# MySensors_AirQuality_Board_2017-11-14.net
KiCad netlist of a schematic drawn in EAGLE
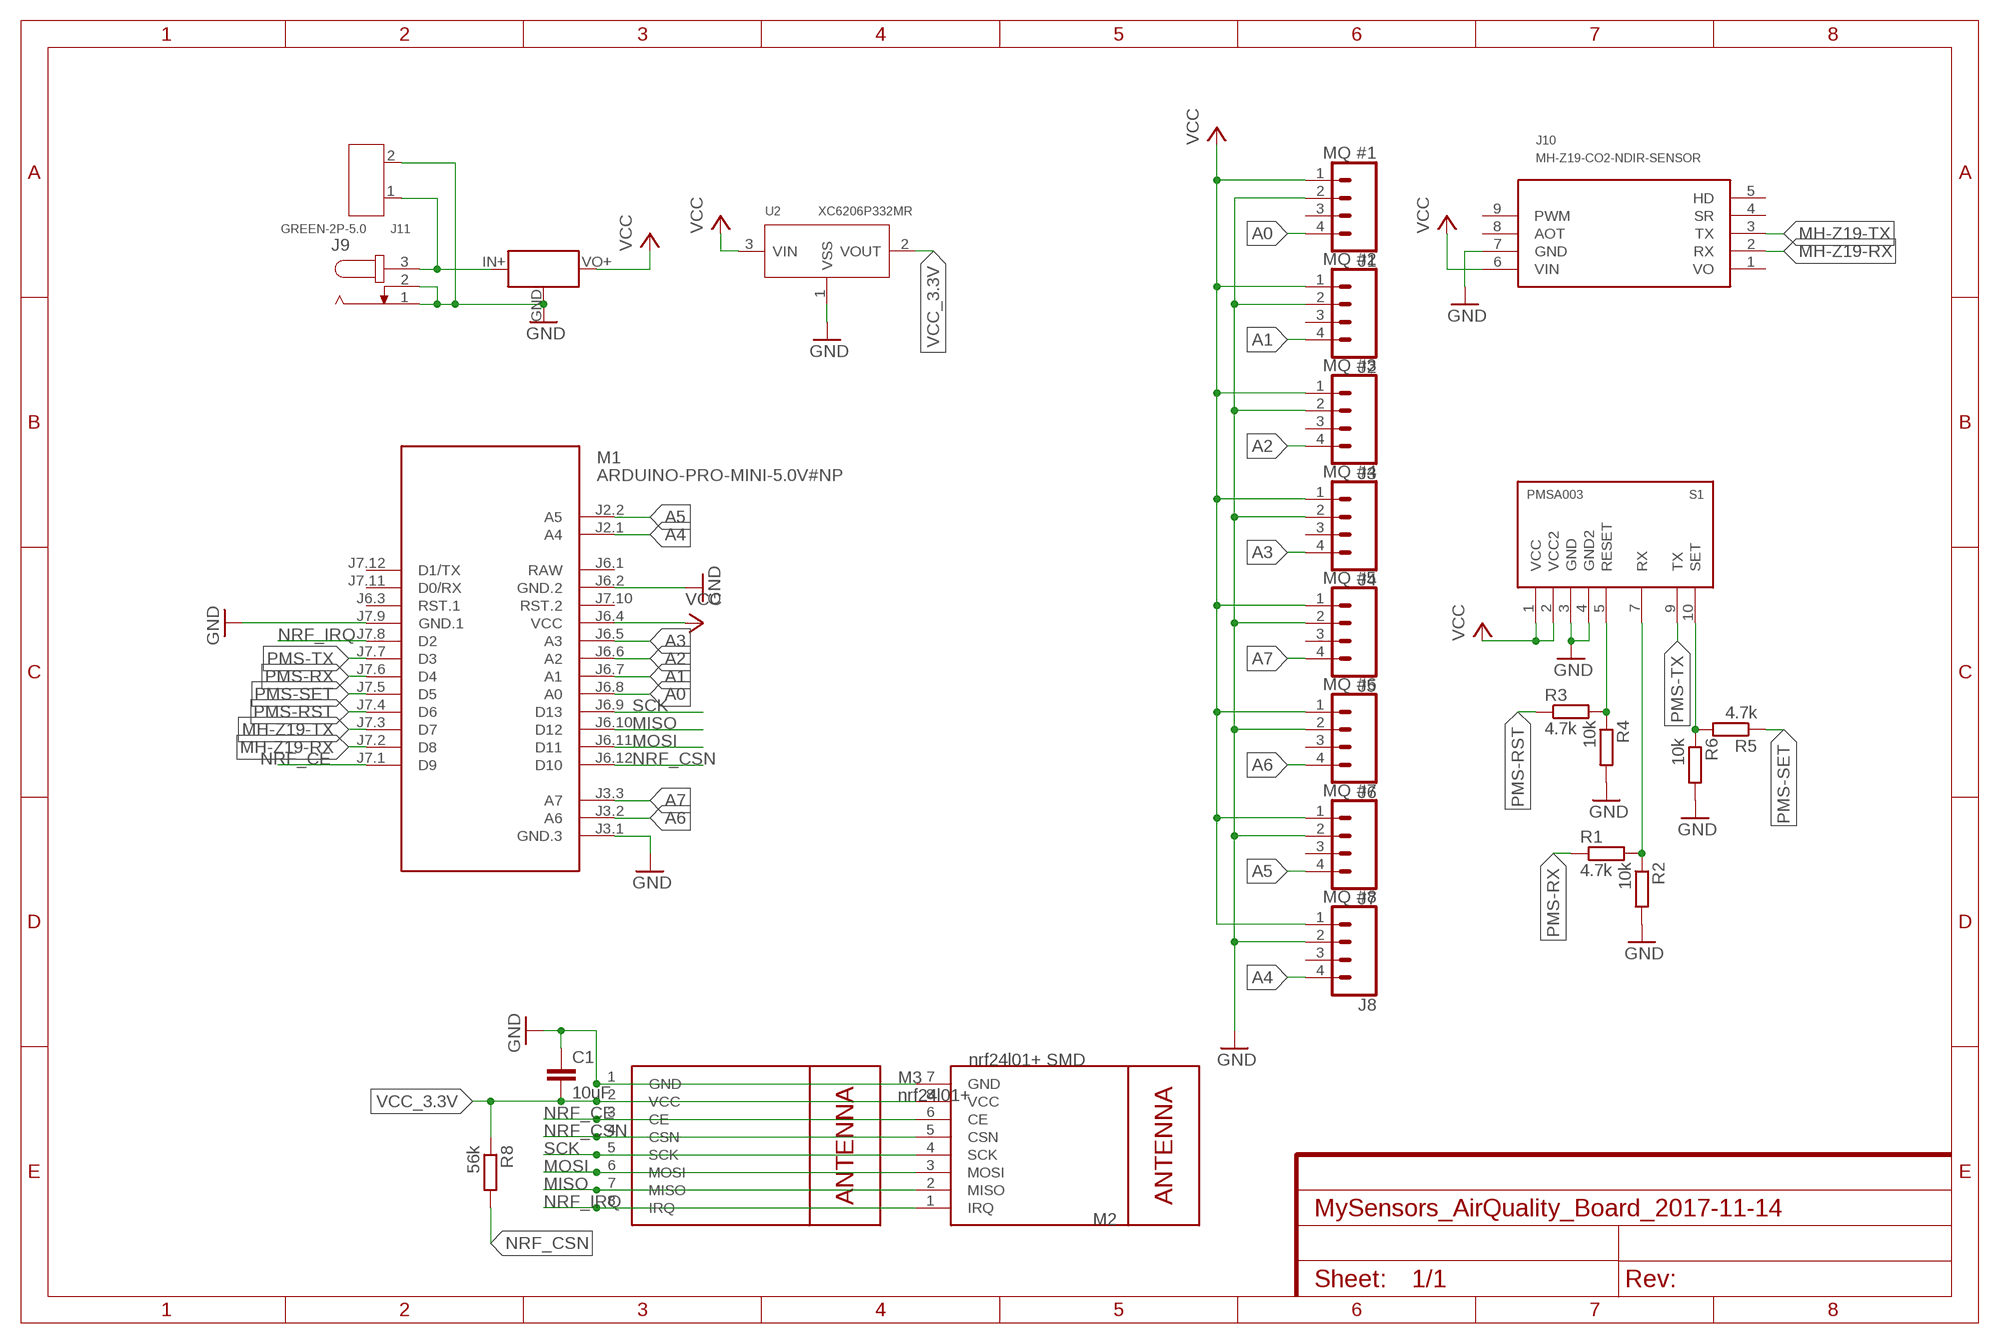
[diagram p0: schematic, sheet 1]

(export (version "E")
  (design (tool "Eeschema 10.0.6"))
  (components
    (comp (ref "C1")
      (value "10uF")
      (footprint "eagle-import:C0805")
      (libsource (lib "eagle-import") (part "C-EUC0805"))
    )
    (comp (ref "J1")
      (value "MQ #1")
      (footprint "eagle-import:1X04")
      (libsource (lib "eagle-import") (part "CONN_04"))
    )
    (comp (ref "J2")
      (value "MQ #2")
      (footprint "eagle-import:1X04")
      (libsource (lib "eagle-import") (part "CONN_04"))
    )
    (comp (ref "J3")
      (value "MQ #3")
      (footprint "eagle-import:1X04")
      (libsource (lib "eagle-import") (part "CONN_04"))
    )
    (comp (ref "J4")
      (value "MQ #4")
      (footprint "eagle-import:1X04")
      (libsource (lib "eagle-import") (part "CONN_04"))
    )
    (comp (ref "J5")
      (value "MQ #5")
      (footprint "eagle-import:1X04")
      (libsource (lib "eagle-import") (part "CONN_04"))
    )
    (comp (ref "J6")
      (value "MQ #6")
      (footprint "eagle-import:1X04")
      (libsource (lib "eagle-import") (part "CONN_04"))
    )
    (comp (ref "J7")
      (value "MQ #7")
      (footprint "eagle-import:1X04")
      (libsource (lib "eagle-import") (part "CONN_04"))
    )
    (comp (ref "J8")
      (value "MQ #8")
      (footprint "eagle-import:1X04")
      (libsource (lib "eagle-import") (part "CONN_04"))
    )
    (comp (ref "J9")
      (value "JACK-PLUG1")
      (footprint "eagle-import:SPC4078")
      (libsource (lib "eagle-import") (part "JACK-PLUG1"))
    )
    (comp (ref "J10")
      (value "MH-Z19-CO2-NDIR-SENSOR")
      (footprint "eagle-import:MH-Z19")
      (libsource (lib "eagle-import") (part "MH-Z19-CO2-NDIR-SENSOR"))
    )
    (comp (ref "J11")
      (value "GREEN-2P-5.0")
      (footprint "eagle-import:H2-5.0-10.5X8.0MM")
      (libsource (lib "eagle-import") (part "SCREW-TERMINAL-GREEN(2P-5.0)"))
    )
    (comp (ref "M1")
      (value "ARDUINO-PRO-MINI-5.0V#NP")
      (footprint "eagle-import:ARDUINO-PRO-MINI#NP")
      (libsource (lib "eagle-import") (part "ARDUINO-PRO-MINI-#NP5.0V"))
    )
    (comp (ref "M2")
      (value "nrf24l01+ SMD")
      (footprint "eagle-import:WIRELESS-NRF24L01-SMD")
      (libsource (lib "eagle-import") (part "WIRELESS-NRF24L01SMD"))
    )
    (comp (ref "M3")
      (value "nrf24l01+")
      (footprint "eagle-import:WIRELESS-NRF24L01")
      (libsource (lib "eagle-import") (part "WIRELESS-NRF24L01STANDARD"))
    )
    (comp (ref "R1")
      (value "4.7k")
      (footprint "eagle-import:R0805")
      (libsource (lib "eagle-import") (part "resistor_348_R-EU_R0805"))
    )
    (comp (ref "R2")
      (value "10k")
      (footprint "eagle-import:R0805")
      (libsource (lib "eagle-import") (part "resistor_348_R-EU_R0805"))
    )
    (comp (ref "R3")
      (value "4.7k")
      (footprint "eagle-import:R0805")
      (libsource (lib "eagle-import") (part "resistor_348_R-EU_R0805"))
    )
    (comp (ref "R4")
      (value "10k")
      (footprint "eagle-import:R0805")
      (libsource (lib "eagle-import") (part "resistor_348_R-EU_R0805"))
    )
    (comp (ref "R5")
      (value "4.7k")
      (footprint "eagle-import:R0805")
      (libsource (lib "eagle-import") (part "resistor_348_R-EU_R0805"))
    )
    (comp (ref "R6")
      (value "10k")
      (footprint "eagle-import:R0805")
      (libsource (lib "eagle-import") (part "resistor_348_R-EU_R0805"))
    )
    (comp (ref "R8")
      (value "56k")
      (footprint "eagle-import:R0805")
      (libsource (lib "eagle-import") (part "R-EU_R0805"))
    )
    (comp (ref "S1")
      (value "PMSA003")
      (footprint "eagle-import:PMSA003")
      (libsource (lib "eagle-import") (part "PMSA003"))
    )
    (comp (ref "U$2")
      (value "MINI_BUCK_CONVERTER")
      (footprint "eagle-import:MINI_BUCK_CONVERTER")
      (libsource (lib "eagle-import") (part "MINI_BUCK_CONVERTER"))
    )
    (comp (ref "U2")
      (value "XC6206P332MR")
      (footprint "eagle-import:SOT-23")
      (fields (field (name "MPN") "XC6206P332MR-G"))
      (libsource (lib "eagle-import") (part "PMIC-LDO-XC6206P332MR-G(SOT23)"))
    )
  )
  (nets
    (net (code "1") (name "/MISO") (class "Default")
      (node (ref "M1") (pin "J6.10") (pinfunction "D12_J6.10") (pintype "bidirectional"))
      (node (ref "M2") (pin "2") (pinfunction "MISO_2") (pintype "bidirectional"))
      (node (ref "M3") (pin "7") (pinfunction "MISO_7") (pintype "bidirectional"))
    )
    (net (code "2") (name "/MOSI") (class "Default")
      (node (ref "M1") (pin "J6.11") (pinfunction "D11_J6.11") (pintype "bidirectional"))
      (node (ref "M2") (pin "3") (pinfunction "MOSI_3") (pintype "bidirectional"))
      (node (ref "M3") (pin "6") (pinfunction "MOSI_6") (pintype "bidirectional"))
    )
    (net (code "3") (name "/NRF_CE") (class "Default")
      (node (ref "M1") (pin "J7.1") (pinfunction "D9_J7.1") (pintype "bidirectional"))
      (node (ref "M2") (pin "6") (pinfunction "CE_6") (pintype "bidirectional"))
      (node (ref "M3") (pin "3") (pinfunction "CE_3") (pintype "bidirectional"))
    )
    (net (code "4") (name "/NRF_IRQ") (class "Default")
      (node (ref "M1") (pin "J7.8") (pinfunction "D2_J7.8") (pintype "bidirectional"))
      (node (ref "M2") (pin "1") (pinfunction "IRQ_1") (pintype "bidirectional"))
      (node (ref "M3") (pin "8") (pinfunction "IRQ_8") (pintype "bidirectional"))
    )
    (net (code "5") (name "/RAW") (class "Default")
      (node (ref "M1") (pin "J6.1") (pinfunction "RAW_J6.1") (pintype "power_in"))
    )
    (net (code "6") (name "/SCK") (class "Default")
      (node (ref "M1") (pin "J6.9") (pinfunction "D13_J6.9") (pintype "bidirectional"))
      (node (ref "M2") (pin "4") (pinfunction "SCK_4") (pintype "bidirectional"))
      (node (ref "M3") (pin "5") (pinfunction "SCK_5") (pintype "bidirectional"))
    )
    (net (code "7") (name "/VO") (class "Default")
      (node (ref "J10") (pin "1") (pinfunction "VO_1") (pintype "power_in"))
    )
    (net (code "8") (name "A0") (class "Default")
      (node (ref "J1") (pin "4") (pinfunction "4_4") (pintype "passive"))
      (node (ref "M1") (pin "J6.8") (pinfunction "A0_J6.8") (pintype "bidirectional"))
    )
    (net (code "9") (name "A1") (class "Default")
      (node (ref "J2") (pin "4") (pinfunction "4_4") (pintype "passive"))
      (node (ref "M1") (pin "J6.7") (pinfunction "A1_J6.7") (pintype "bidirectional"))
    )
    (net (code "10") (name "A2") (class "Default")
      (node (ref "J3") (pin "4") (pinfunction "4_4") (pintype "passive"))
      (node (ref "M1") (pin "J6.6") (pinfunction "A2_J6.6") (pintype "bidirectional"))
    )
    (net (code "11") (name "A3") (class "Default")
      (node (ref "J4") (pin "4") (pinfunction "4_4") (pintype "passive"))
      (node (ref "M1") (pin "J6.5") (pinfunction "A3_J6.5") (pintype "bidirectional"))
    )
    (net (code "12") (name "A4") (class "Default")
      (node (ref "J8") (pin "4") (pinfunction "4_4") (pintype "passive"))
      (node (ref "M1") (pin "J2.1") (pinfunction "A4_J2.1") (pintype "bidirectional"))
    )
    (net (code "13") (name "A5") (class "Default")
      (node (ref "J7") (pin "4") (pinfunction "4_4") (pintype "passive"))
      (node (ref "M1") (pin "J2.2") (pinfunction "A5_J2.2") (pintype "bidirectional"))
    )
    (net (code "14") (name "A6") (class "Default")
      (node (ref "J6") (pin "4") (pinfunction "4_4") (pintype "passive"))
      (node (ref "M1") (pin "J3.2") (pinfunction "A6_J3.2") (pintype "bidirectional"))
    )
    (net (code "15") (name "A7") (class "Default")
      (node (ref "J5") (pin "4") (pinfunction "4_4") (pintype "passive"))
      (node (ref "M1") (pin "J3.3") (pinfunction "A7_J3.3") (pintype "bidirectional"))
    )
    (net (code "16") (name "GND") (class "Default")
      (node (ref "C1") (pin "1") (pinfunction "1_1") (pintype "passive"))
      (node (ref "J1") (pin "2") (pinfunction "2_2") (pintype "passive"))
      (node (ref "J10") (pin "7") (pinfunction "GND_7") (pintype "power_in"))
      (node (ref "J11") (pin "2") (pinfunction "2_2") (pintype "bidirectional"))
      (node (ref "J2") (pin "2") (pinfunction "2_2") (pintype "passive"))
      (node (ref "J3") (pin "2") (pinfunction "2_2") (pintype "passive"))
      (node (ref "J4") (pin "2") (pinfunction "2_2") (pintype "passive"))
      (node (ref "J5") (pin "2") (pinfunction "2_2") (pintype "passive"))
      (node (ref "J6") (pin "2") (pinfunction "2_2") (pintype "passive"))
      (node (ref "J7") (pin "2") (pinfunction "2_2") (pintype "passive"))
      (node (ref "J8") (pin "2") (pinfunction "2_2") (pintype "passive"))
      (node (ref "J9") (pin "1") (pinfunction "1_1") (pintype "passive"))
      (node (ref "J9") (pin "2") (pinfunction "2_2") (pintype "passive"))
      (node (ref "M1") (pin "J3.1") (pinfunction "GND.3_J3.1") (pintype "bidirectional"))
      (node (ref "M1") (pin "J6.2") (pinfunction "GND.2_J6.2") (pintype "power_in"))
      (node (ref "M1") (pin "J7.9") (pinfunction "GND.1_J7.9") (pintype "power_in"))
      (node (ref "M2") (pin "7") (pinfunction "GND_7") (pintype "power_in"))
      (node (ref "M3") (pin "1") (pinfunction "GND_1") (pintype "power_in"))
      (node (ref "R2") (pin "2") (pinfunction "2_2") (pintype "passive"))
      (node (ref "R4") (pin "2") (pinfunction "2_2") (pintype "passive"))
      (node (ref "R6") (pin "2") (pinfunction "2_2") (pintype "passive"))
      (node (ref "S1") (pin "3") (pinfunction "GND_3") (pintype "bidirectional"))
      (node (ref "S1") (pin "4") (pinfunction "GND2_4") (pintype "bidirectional"))
      (node (ref "U$2") (pin "GND") (pinfunction "GND_GND") (pintype "bidirectional"))
      (node (ref "U2") (pin "1") (pinfunction "VSS_1") (pintype "power_in"))
    )
    (net (code "17") (name "MH-Z19-RX") (class "Default")
      (node (ref "J10") (pin "2") (pinfunction "RX_2") (pintype "input"))
      (node (ref "M1") (pin "J7.2") (pinfunction "D8_J7.2") (pintype "bidirectional"))
    )
    (net (code "18") (name "MH-Z19-TX") (class "Default")
      (node (ref "J10") (pin "3") (pinfunction "TX_3") (pintype "output"))
      (node (ref "M1") (pin "J7.3") (pinfunction "D7_J7.3") (pintype "bidirectional"))
    )
    (net (code "19") (name "NRF_CSN") (class "Default")
      (node (ref "M1") (pin "J6.12") (pinfunction "D10_J6.12") (pintype "bidirectional"))
      (node (ref "M2") (pin "5") (pinfunction "CSN_5") (pintype "bidirectional"))
      (node (ref "M3") (pin "4") (pinfunction "CSN_4") (pintype "bidirectional"))
      (node (ref "R8") (pin "2") (pinfunction "2_2") (pintype "passive"))
    )
    (net (code "20") (name "Net-(S1-RESET)") (class "Default")
      (node (ref "R3") (pin "2") (pinfunction "2_2") (pintype "passive"))
      (node (ref "R4") (pin "1") (pinfunction "1_1") (pintype "passive"))
      (node (ref "S1") (pin "5") (pinfunction "RESET_5") (pintype "bidirectional"))
    )
    (net (code "21") (name "Net-(S1-RX)") (class "Default")
      (node (ref "R1") (pin "2") (pinfunction "2_2") (pintype "passive"))
      (node (ref "R2") (pin "1") (pinfunction "1_1") (pintype "passive"))
      (node (ref "S1") (pin "7") (pinfunction "RX_7") (pintype "bidirectional"))
    )
    (net (code "22") (name "Net-(S1-SET)") (class "Default")
      (node (ref "R5") (pin "2") (pinfunction "2_2") (pintype "passive"))
      (node (ref "R6") (pin "1") (pinfunction "1_1") (pintype "passive"))
      (node (ref "S1") (pin "10") (pinfunction "SET_10") (pintype "bidirectional"))
    )
    (net (code "23") (name "Net-(U$2-VIN)") (class "Default")
      (node (ref "J11") (pin "1") (pinfunction "1_1") (pintype "bidirectional"))
      (node (ref "J9") (pin "3") (pinfunction "3_3") (pintype "passive"))
      (node (ref "U$2") (pin "IN+") (pinfunction "VIN_IN+") (pintype "input"))
    )
    (net (code "24") (name "PMS-RST") (class "Default")
      (node (ref "M1") (pin "J7.4") (pinfunction "D6_J7.4") (pintype "bidirectional"))
      (node (ref "R3") (pin "1") (pinfunction "1_1") (pintype "passive"))
    )
    (net (code "25") (name "PMS-RX") (class "Default")
      (node (ref "M1") (pin "J7.6") (pinfunction "D4_J7.6") (pintype "bidirectional"))
      (node (ref "R1") (pin "1") (pinfunction "1_1") (pintype "passive"))
    )
    (net (code "26") (name "PMS-SET") (class "Default")
      (node (ref "M1") (pin "J7.5") (pinfunction "D5_J7.5") (pintype "bidirectional"))
      (node (ref "R5") (pin "1") (pinfunction "1_1") (pintype "passive"))
    )
    (net (code "27") (name "PMS-TX") (class "Default")
      (node (ref "M1") (pin "J7.7") (pinfunction "D3_J7.7") (pintype "bidirectional"))
      (node (ref "S1") (pin "9") (pinfunction "TX_9") (pintype "bidirectional"))
    )
    (net (code "28") (name "VCC") (class "Default")
      (node (ref "J1") (pin "1") (pinfunction "1_1") (pintype "passive"))
      (node (ref "J10") (pin "6") (pinfunction "VIN_6") (pintype "power_in"))
      (node (ref "J2") (pin "1") (pinfunction "1_1") (pintype "passive"))
      (node (ref "J3") (pin "1") (pinfunction "1_1") (pintype "passive"))
      (node (ref "J4") (pin "1") (pinfunction "1_1") (pintype "passive"))
      (node (ref "J5") (pin "1") (pinfunction "1_1") (pintype "passive"))
      (node (ref "J6") (pin "1") (pinfunction "1_1") (pintype "passive"))
      (node (ref "J7") (pin "1") (pinfunction "1_1") (pintype "passive"))
      (node (ref "J8") (pin "1") (pinfunction "1_1") (pintype "passive"))
      (node (ref "M1") (pin "J6.4") (pinfunction "VCC_J6.4") (pintype "power_in"))
      (node (ref "S1") (pin "1") (pinfunction "VCC_1") (pintype "bidirectional"))
      (node (ref "S1") (pin "2") (pinfunction "VCC2_2") (pintype "bidirectional"))
      (node (ref "U$2") (pin "VO+") (pinfunction "VOUT_VO+") (pintype "power_in"))
      (node (ref "U2") (pin "3") (pinfunction "VIN_3") (pintype "input"))
    )
    (net (code "29") (name "VCC_3.3V") (class "Default")
      (node (ref "C1") (pin "2") (pinfunction "2_2") (pintype "passive"))
      (node (ref "M2") (pin "8") (pinfunction "VCC_8") (pintype "power_in"))
      (node (ref "M3") (pin "2") (pinfunction "VCC_2") (pintype "power_in"))
      (node (ref "R8") (pin "1") (pinfunction "1_1") (pintype "passive"))
      (node (ref "U2") (pin "2") (pinfunction "VOUT_2") (pintype "output"))
    )
    (net (code "30") (name "unconnected-(J1-Pad3)") (class "Default")
      (node (ref "J1") (pin "3") (pinfunction "3_3") (pintype "passive"))
    )
    (net (code "31") (name "unconnected-(J2-Pad3)") (class "Default")
      (node (ref "J2") (pin "3") (pinfunction "3_3") (pintype "passive"))
    )
    (net (code "32") (name "unconnected-(J3-Pad3)") (class "Default")
      (node (ref "J3") (pin "3") (pinfunction "3_3") (pintype "passive"))
    )
    (net (code "33") (name "unconnected-(J4-Pad3)") (class "Default")
      (node (ref "J4") (pin "3") (pinfunction "3_3") (pintype "passive"))
    )
    (net (code "34") (name "unconnected-(J5-Pad3)") (class "Default")
      (node (ref "J5") (pin "3") (pinfunction "3_3") (pintype "passive"))
    )
    (net (code "35") (name "unconnected-(J6-Pad3)") (class "Default")
      (node (ref "J6") (pin "3") (pinfunction "3_3") (pintype "passive"))
    )
    (net (code "36") (name "unconnected-(J7-Pad3)") (class "Default")
      (node (ref "J7") (pin "3") (pinfunction "3_3") (pintype "passive"))
    )
    (net (code "37") (name "unconnected-(J8-Pad3)") (class "Default")
      (node (ref "J8") (pin "3") (pinfunction "3_3") (pintype "passive"))
    )
    (net (code "38") (name "unconnected-(J10-AOT-Pad8)") (class "Default")
      (node (ref "J10") (pin "8") (pinfunction "AOT_8") (pintype "no_connect"))
    )
    (net (code "39") (name "unconnected-(J10-HD-Pad5)") (class "Default")
      (node (ref "J10") (pin "5") (pinfunction "HD_5") (pintype "input"))
    )
    (net (code "40") (name "unconnected-(J10-PWM-Pad9)") (class "Default")
      (node (ref "J10") (pin "9") (pinfunction "PWM_9") (pintype "output"))
    )
    (net (code "41") (name "unconnected-(J10-SR-Pad4)") (class "Default")
      (node (ref "J10") (pin "4") (pinfunction "SR_4") (pintype "no_connect"))
    )
    (net (code "42") (name "unconnected-(M1-D0{slash}RX-PadJ7.11)") (class "Default")
      (node (ref "M1") (pin "J7.11") (pinfunction "D0/RX_J7.11") (pintype "bidirectional"))
    )
    (net (code "43") (name "unconnected-(M1-D1{slash}TX-PadJ7.12)") (class "Default")
      (node (ref "M1") (pin "J7.12") (pinfunction "D1/TX_J7.12") (pintype "bidirectional"))
    )
    (net (code "44") (name "unconnected-(M1-RST.1-PadJ6.3)") (class "Default")
      (node (ref "M1") (pin "J6.3") (pinfunction "RST.1_J6.3") (pintype "bidirectional"))
    )
    (net (code "45") (name "unconnected-(M1-RST.2-PadJ7.10)") (class "Default")
      (node (ref "M1") (pin "J7.10") (pinfunction "RST.2_J7.10") (pintype "bidirectional"))
    )
  )
)
